# ADSR2.net
KiCad netlist of a schematic drawn in EAGLE
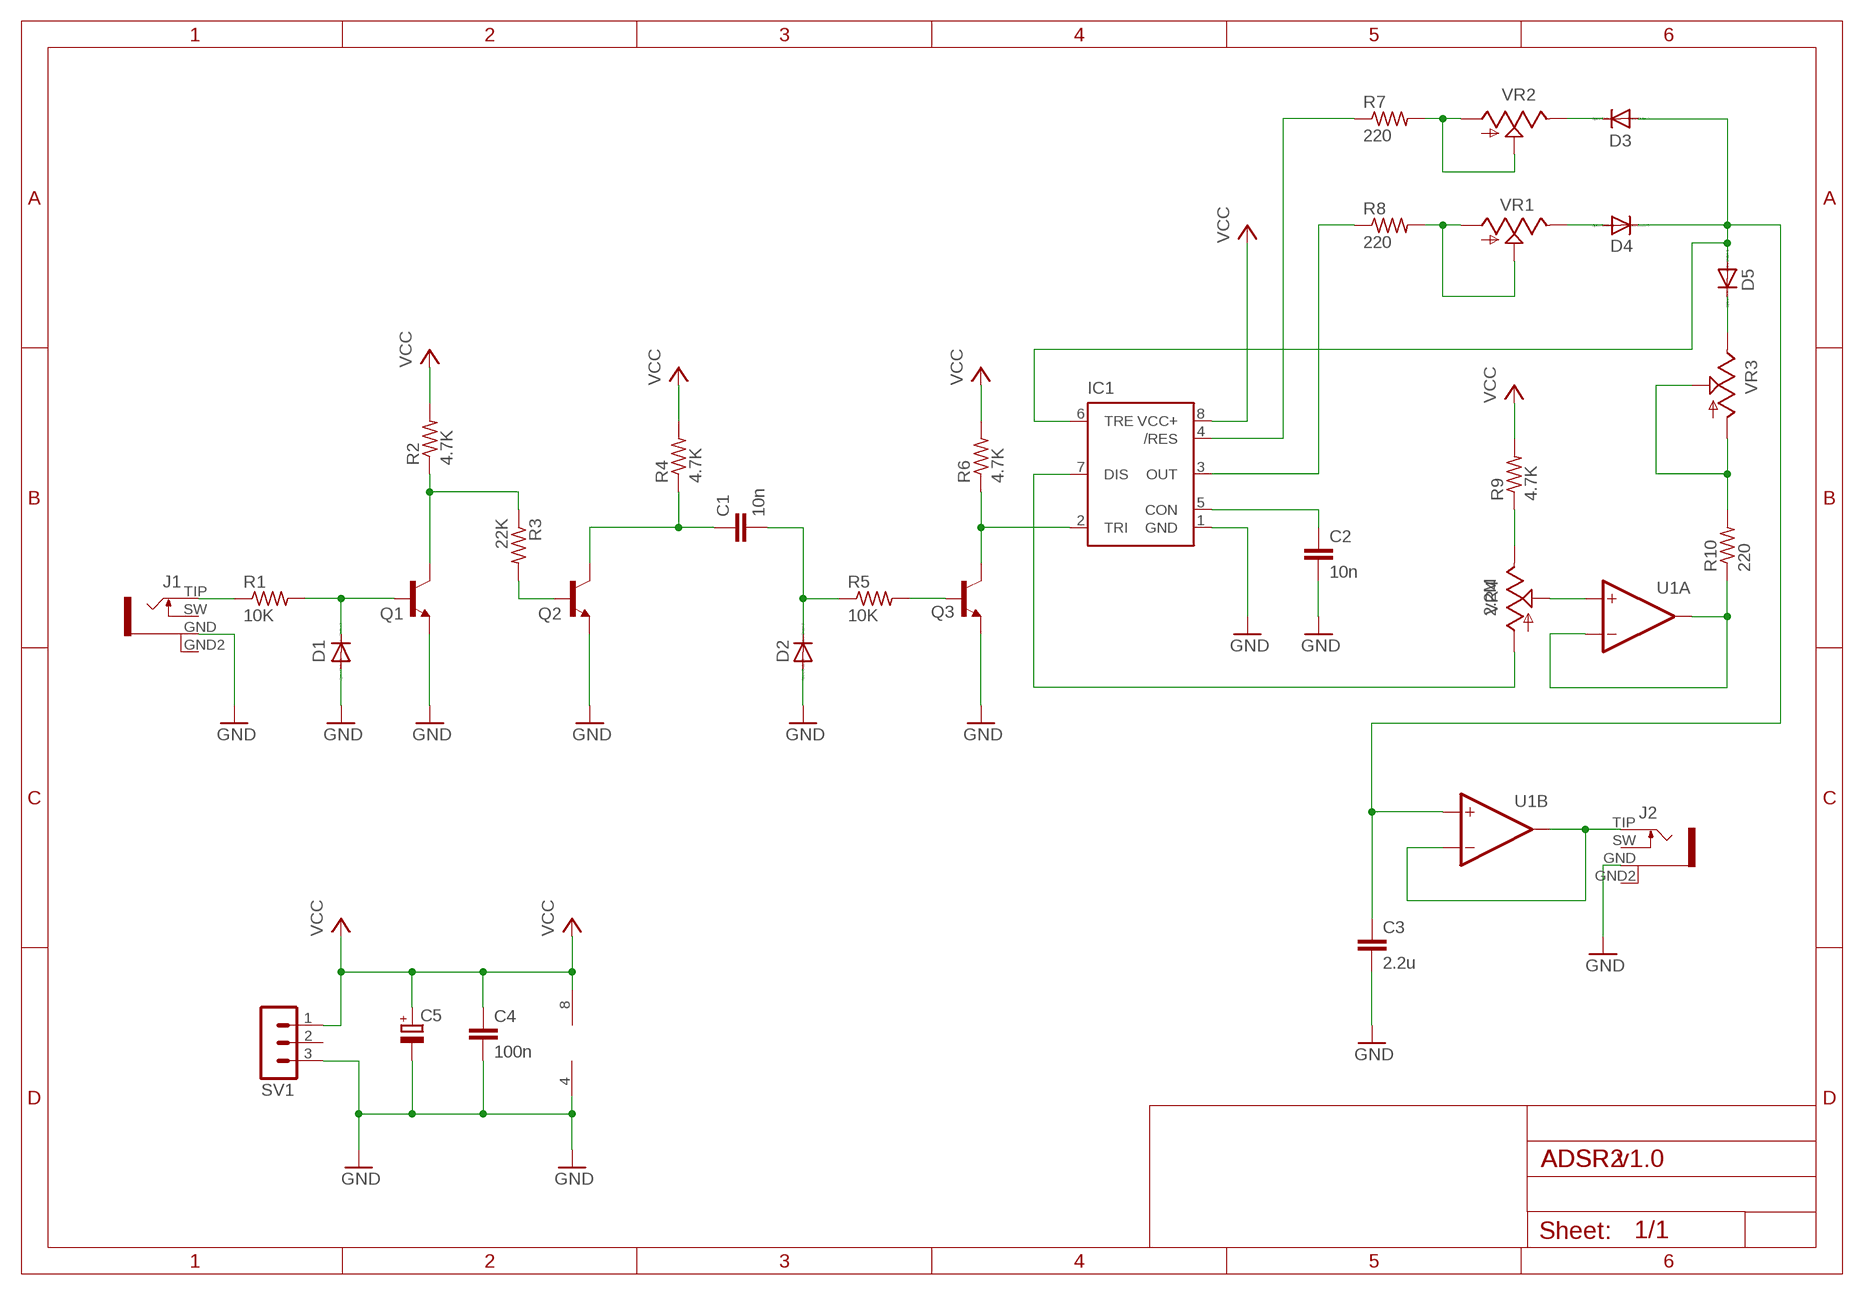
[diagram p0: schematic, sheet 1]

(export (version "E")
  (design (tool "Eeschema 10.0.6"))
  (components
    (comp (ref "C1")
      (value "10n")
      (footprint "eagle-import:C025-025X050")
      (libsource (lib "eagle-import") (part "C-EU025-025X050"))
    )
    (comp (ref "C2")
      (value "10n")
      (footprint "eagle-import:C025-025X050")
      (libsource (lib "eagle-import") (part "C-EU025-025X050"))
    )
    (comp (ref "C3")
      (value "2.2u")
      (footprint "eagle-import:C025-025X050")
      (libsource (lib "eagle-import") (part "C-EU025-025X050"))
    )
    (comp (ref "C4")
      (value "100n")
      (footprint "eagle-import:C025-025X050")
      (libsource (lib "eagle-import") (part "C-EU025-025X050"))
    )
    (comp (ref "C5")
      (value "CPOL-EUE2,5-6E")
      (footprint "eagle-import:E2,5-6E")
      (libsource (lib "eagle-import") (part "CPOL-EUE2,5-6E"))
    )
    (comp (ref "D1")
      (value "1N4148DO35-7")
      (footprint "eagle-import:DO35-7")
      (libsource (lib "eagle-import") (part "1N4148DO35-7"))
    )
    (comp (ref "D2")
      (value "1N4148DO35-7")
      (footprint "eagle-import:DO35-7")
      (libsource (lib "eagle-import") (part "1N4148DO35-7"))
    )
    (comp (ref "D3")
      (value "1N4148DO35-7")
      (footprint "eagle-import:DO35-7")
      (libsource (lib "eagle-import") (part "1N4148DO35-7"))
    )
    (comp (ref "D4")
      (value "1N4148DO35-7")
      (footprint "eagle-import:DO35-7")
      (libsource (lib "eagle-import") (part "1N4148DO35-7"))
    )
    (comp (ref "D5")
      (value "1N4148DO35-7")
      (footprint "eagle-import:DO35-7")
      (libsource (lib "eagle-import") (part "1N4148DO35-7"))
    )
    (comp (ref "IC1")
      (value "555")
      (footprint "eagle-import:DIP08")
      (libsource (lib "eagle-import") (part "555P"))
    )
    (comp (ref "J1")
      (value "PJ301WQP")
      (footprint "eagle-import:THONK_JACK_P")
      (libsource (lib "eagle-import") (part "PJ301WQP"))
    )
    (comp (ref "J2")
      (value "PJ301WQP")
      (footprint "eagle-import:THONK_JACK_P")
      (libsource (lib "eagle-import") (part "PJ301WQP"))
    )
    (comp (ref "Q1")
      (value "2N3904_TO92")
      (footprint "eagle-import:TO92-EBC")
      (libsource (lib "eagle-import") (part "2N3904_TO92"))
    )
    (comp (ref "Q2")
      (value "2N3904_TO92")
      (footprint "eagle-import:TO92-EBC")
      (libsource (lib "eagle-import") (part "2N3904_TO92"))
    )
    (comp (ref "Q3")
      (value "2N3904_TO92")
      (footprint "eagle-import:TO92-EBC")
      (libsource (lib "eagle-import") (part "2N3904_TO92"))
    )
    (comp (ref "R1")
      (value "10K")
      (footprint "eagle-import:0207_10")
      (libsource (lib "eagle-import") (part "R-US_0207/10"))
    )
    (comp (ref "R2")
      (value "4.7K")
      (footprint "eagle-import:0207_10")
      (libsource (lib "eagle-import") (part "R-US_0207/10"))
    )
    (comp (ref "R3")
      (value "22K")
      (footprint "eagle-import:0207_10")
      (libsource (lib "eagle-import") (part "R-US_0207/10"))
    )
    (comp (ref "R4")
      (value "4.7K")
      (footprint "eagle-import:0207_10")
      (libsource (lib "eagle-import") (part "R-US_0207/10"))
    )
    (comp (ref "R5")
      (value "10K")
      (footprint "eagle-import:0207_10")
      (libsource (lib "eagle-import") (part "R-US_0207/10"))
    )
    (comp (ref "R6")
      (value "4.7K")
      (footprint "eagle-import:0207_10")
      (libsource (lib "eagle-import") (part "R-US_0207/10"))
    )
    (comp (ref "R7")
      (value "220")
      (footprint "eagle-import:0207_10")
      (libsource (lib "eagle-import") (part "R-US_0207/10"))
    )
    (comp (ref "R8")
      (value "220")
      (footprint "eagle-import:0207_10")
      (libsource (lib "eagle-import") (part "R-US_0207/10"))
    )
    (comp (ref "R9")
      (value "4.7K")
      (footprint "eagle-import:0207_10")
      (libsource (lib "eagle-import") (part "R-US_0207/10"))
    )
    (comp (ref "R10")
      (value "220")
      (footprint "eagle-import:0207_10")
      (libsource (lib "eagle-import") (part "R-US_0207/10"))
    )
    (comp (ref "SV1")
      (value "MA03-1")
      (footprint "eagle-import:MA03-1")
      (libsource (lib "eagle-import") (part "MA03-1"))
    )
    (comp (ref "U1")
      (value "TL072_DIL08")
      (footprint "eagle-import:DIL08")
      (libsource (lib "eagle-import") (part "TL072_DIL08"))
    )
    (comp (ref "VR1")
      (value "9MM_SNAP-IN_POT_")
      (footprint "eagle-import:9MM_SNAP-IN_POT")
      (libsource (lib "eagle-import") (part "9MM_SNAP-IN_POT_"))
    )
    (comp (ref "VR2")
      (value "9MM_SNAP-IN_POT_")
      (footprint "eagle-import:9MM_SNAP-IN_POT")
      (libsource (lib "eagle-import") (part "9MM_SNAP-IN_POT_"))
    )
    (comp (ref "VR3")
      (value "9MM_SNAP-IN_POT_")
      (footprint "eagle-import:9MM_SNAP-IN_POT")
      (libsource (lib "eagle-import") (part "9MM_SNAP-IN_POT_"))
    )
    (comp (ref "VR4")
      (value "2.2M")
      (footprint "eagle-import:9MM_SNAP-IN_POT")
      (libsource (lib "eagle-import") (part "9MM_SNAP-IN_POT_"))
    )
  )
  (nets
    (net (code "1") (name "GND") (class "Default")
      (node (ref "C2") (pin "2") (pinfunction "2_2") (pintype "passive"))
      (node (ref "C3") (pin "2") (pinfunction "2_2") (pintype "passive"))
      (node (ref "C4") (pin "2") (pinfunction "2_2") (pintype "passive"))
      (node (ref "C5") (pin "-") (pinfunction "-_-") (pintype "passive"))
      (node (ref "D1") (pin "A") (pinfunction "A_A") (pintype "passive"))
      (node (ref "D2") (pin "A") (pinfunction "A_A") (pintype "passive"))
      (node (ref "IC1") (pin "1") (pinfunction "GND_1") (pintype "power_in"))
      (node (ref "J1") (pin "GND") (pinfunction "1_GND") (pintype "passive"))
      (node (ref "J2") (pin "GND") (pinfunction "1_GND") (pintype "passive"))
      (node (ref "Q1") (pin "E") (pinfunction "E_E") (pintype "passive"))
      (node (ref "Q2") (pin "E") (pinfunction "E_E") (pintype "passive"))
      (node (ref "Q3") (pin "E") (pinfunction "E_E") (pintype "passive"))
      (node (ref "SV1") (pin "3") (pinfunction "3_3") (pintype "passive"))
      (node (ref "U1") (pin "4") (pinfunction "V-_4") (pintype "power_in"))
    )
    (net (code "2") (name "Net-(C1-Pad1)") (class "Default")
      (node (ref "C1") (pin "1") (pinfunction "1_1") (pintype "passive"))
      (node (ref "Q2") (pin "C") (pinfunction "C_C") (pintype "passive"))
      (node (ref "R4") (pin "1") (pinfunction "1_1") (pintype "passive"))
    )
    (net (code "3") (name "Net-(C1-Pad2)") (class "Default")
      (node (ref "C1") (pin "2") (pinfunction "2_2") (pintype "passive"))
      (node (ref "D2") (pin "C") (pinfunction "C_C") (pintype "passive"))
      (node (ref "R5") (pin "1") (pinfunction "1_1") (pintype "passive"))
    )
    (net (code "4") (name "Net-(D1-PadC)") (class "Default")
      (node (ref "D1") (pin "C") (pinfunction "C_C") (pintype "passive"))
      (node (ref "Q1") (pin "B") (pinfunction "B_B") (pintype "passive"))
      (node (ref "R1") (pin "2") (pinfunction "2_2") (pintype "passive"))
    )
    (net (code "5") (name "Net-(IC1-CON)") (class "Default")
      (node (ref "C2") (pin "1") (pinfunction "1_1") (pintype "passive"))
      (node (ref "IC1") (pin "5") (pinfunction "CON_5") (pintype "input"))
    )
    (net (code "6") (name "Net-(IC1-DIS)") (class "Default")
      (node (ref "IC1") (pin "7") (pinfunction "DIS_7") (pintype "input"))
      (node (ref "VR4") (pin "1") (pinfunction "A_1") (pintype "passive"))
    )
    (net (code "7") (name "Net-(IC1-OUT)") (class "Default")
      (node (ref "IC1") (pin "3") (pinfunction "OUT_3") (pintype "output"))
      (node (ref "R8") (pin "1") (pinfunction "1_1") (pintype "passive"))
    )
    (net (code "8") (name "Net-(IC1-TRE)") (class "Default")
      (node (ref "C3") (pin "1") (pinfunction "1_1") (pintype "passive"))
      (node (ref "D3") (pin "A") (pinfunction "A_A") (pintype "passive"))
      (node (ref "D4") (pin "C") (pinfunction "C_C") (pintype "passive"))
      (node (ref "D5") (pin "A") (pinfunction "A_A") (pintype "passive"))
      (node (ref "IC1") (pin "6") (pinfunction "TRE_6") (pintype "input"))
      (node (ref "U1") (pin "5") (pinfunction "+IN_5") (pintype "input"))
    )
    (net (code "9") (name "Net-(IC1-TRI)") (class "Default")
      (node (ref "IC1") (pin "2") (pinfunction "TRI_2") (pintype "input"))
      (node (ref "Q3") (pin "C") (pinfunction "C_C") (pintype "passive"))
      (node (ref "R6") (pin "1") (pinfunction "1_1") (pintype "passive"))
    )
    (net (code "10") (name "Net-(IC1-{slash}RES)") (class "Default")
      (node (ref "IC1") (pin "4") (pinfunction "/RES_4") (pintype "input"))
      (node (ref "R7") (pin "1") (pinfunction "1_1") (pintype "passive"))
    )
    (net (code "11") (name "Net-(J1-2)") (class "Default")
      (node (ref "J1") (pin "TIP") (pinfunction "2_TIP") (pintype "passive"))
      (node (ref "R1") (pin "1") (pinfunction "1_1") (pintype "passive"))
    )
    (net (code "12") (name "Net-(J2-2)") (class "Default")
      (node (ref "J2") (pin "TIP") (pinfunction "2_TIP") (pintype "passive"))
      (node (ref "U1") (pin "6") (pinfunction "-IN_6") (pintype "input"))
      (node (ref "U1") (pin "7") (pinfunction "OUT_7") (pintype "output"))
    )
    (net (code "13") (name "Net-(Q1-PadC)") (class "Default")
      (node (ref "Q1") (pin "C") (pinfunction "C_C") (pintype "passive"))
      (node (ref "R2") (pin "1") (pinfunction "1_1") (pintype "passive"))
      (node (ref "R3") (pin "1") (pinfunction "1_1") (pintype "passive"))
    )
    (net (code "14") (name "Net-(Q2-PadB)") (class "Default")
      (node (ref "Q2") (pin "B") (pinfunction "B_B") (pintype "passive"))
      (node (ref "R3") (pin "2") (pinfunction "2_2") (pintype "passive"))
    )
    (net (code "15") (name "Net-(Q3-PadB)") (class "Default")
      (node (ref "Q3") (pin "B") (pinfunction "B_B") (pintype "passive"))
      (node (ref "R5") (pin "2") (pinfunction "2_2") (pintype "passive"))
    )
    (net (code "16") (name "Net-(U1A-+IN)") (class "Default")
      (node (ref "U1") (pin "3") (pinfunction "+IN_3") (pintype "input"))
      (node (ref "VR4") (pin "2") (pinfunction "S_2") (pintype "passive"))
    )
    (net (code "17") (name "Net-(U1A--IN)") (class "Default")
      (node (ref "R10") (pin "1") (pinfunction "1_1") (pintype "passive"))
      (node (ref "U1") (pin "1") (pinfunction "OUT_1") (pintype "output"))
      (node (ref "U1") (pin "2") (pinfunction "-IN_2") (pintype "input"))
    )
    (net (code "18") (name "Net-(VR1-A)") (class "Default")
      (node (ref "R8") (pin "2") (pinfunction "2_2") (pintype "passive"))
      (node (ref "VR1") (pin "1") (pinfunction "A_1") (pintype "passive"))
      (node (ref "VR1") (pin "2") (pinfunction "S_2") (pintype "passive"))
    )
    (net (code "19") (name "Net-(VR1-E)") (class "Default")
      (node (ref "D4") (pin "A") (pinfunction "A_A") (pintype "passive"))
      (node (ref "VR1") (pin "3") (pinfunction "E_3") (pintype "passive"))
    )
    (net (code "20") (name "Net-(VR2-A)") (class "Default")
      (node (ref "R7") (pin "2") (pinfunction "2_2") (pintype "passive"))
      (node (ref "VR2") (pin "1") (pinfunction "A_1") (pintype "passive"))
      (node (ref "VR2") (pin "2") (pinfunction "S_2") (pintype "passive"))
    )
    (net (code "21") (name "Net-(VR2-E)") (class "Default")
      (node (ref "D3") (pin "C") (pinfunction "C_C") (pintype "passive"))
      (node (ref "VR2") (pin "3") (pinfunction "E_3") (pintype "passive"))
    )
    (net (code "22") (name "Net-(VR3-A)") (class "Default")
      (node (ref "R10") (pin "2") (pinfunction "2_2") (pintype "passive"))
      (node (ref "VR3") (pin "1") (pinfunction "A_1") (pintype "passive"))
      (node (ref "VR3") (pin "2") (pinfunction "S_2") (pintype "passive"))
    )
    (net (code "23") (name "Net-(VR3-E)") (class "Default")
      (node (ref "D5") (pin "C") (pinfunction "C_C") (pintype "passive"))
      (node (ref "VR3") (pin "3") (pinfunction "E_3") (pintype "passive"))
    )
    (net (code "24") (name "Net-(VR4-E)") (class "Default")
      (node (ref "R9") (pin "1") (pinfunction "1_1") (pintype "passive"))
      (node (ref "VR4") (pin "3") (pinfunction "E_3") (pintype "passive"))
    )
    (net (code "25") (name "VCC") (class "Default")
      (node (ref "C4") (pin "1") (pinfunction "1_1") (pintype "passive"))
      (node (ref "C5") (pin "+") (pinfunction "+_+") (pintype "passive"))
      (node (ref "IC1") (pin "8") (pinfunction "VCC+_8") (pintype "power_in"))
      (node (ref "R2") (pin "2") (pinfunction "2_2") (pintype "passive"))
      (node (ref "R4") (pin "2") (pinfunction "2_2") (pintype "passive"))
      (node (ref "R6") (pin "2") (pinfunction "2_2") (pintype "passive"))
      (node (ref "R9") (pin "2") (pinfunction "2_2") (pintype "passive"))
      (node (ref "SV1") (pin "1") (pinfunction "1_1") (pintype "passive"))
      (node (ref "U1") (pin "8") (pinfunction "V+_8") (pintype "power_in"))
    )
    (net (code "26") (name "unconnected-(J1-3-PadSW)") (class "Default")
      (node (ref "J1") (pin "SW") (pinfunction "3_SW") (pintype "passive"))
    )
    (net (code "27") (name "unconnected-(J1-4-PadGND2)") (class "Default")
      (node (ref "J1") (pin "GND2") (pinfunction "4_GND2") (pintype "passive"))
    )
    (net (code "28") (name "unconnected-(J2-3-PadSW)") (class "Default")
      (node (ref "J2") (pin "SW") (pinfunction "3_SW") (pintype "passive"))
    )
    (net (code "29") (name "unconnected-(J2-4-PadGND2)") (class "Default")
      (node (ref "J2") (pin "GND2") (pinfunction "4_GND2") (pintype "passive"))
    )
    (net (code "30") (name "unconnected-(SV1-Pad2)") (class "Default")
      (node (ref "SV1") (pin "2") (pinfunction "2_2") (pintype "passive"))
    )
  )
)
